# synth-zodiac-taurus-cowbell.net
KiCad netlist of a schematic drawn in EAGLE
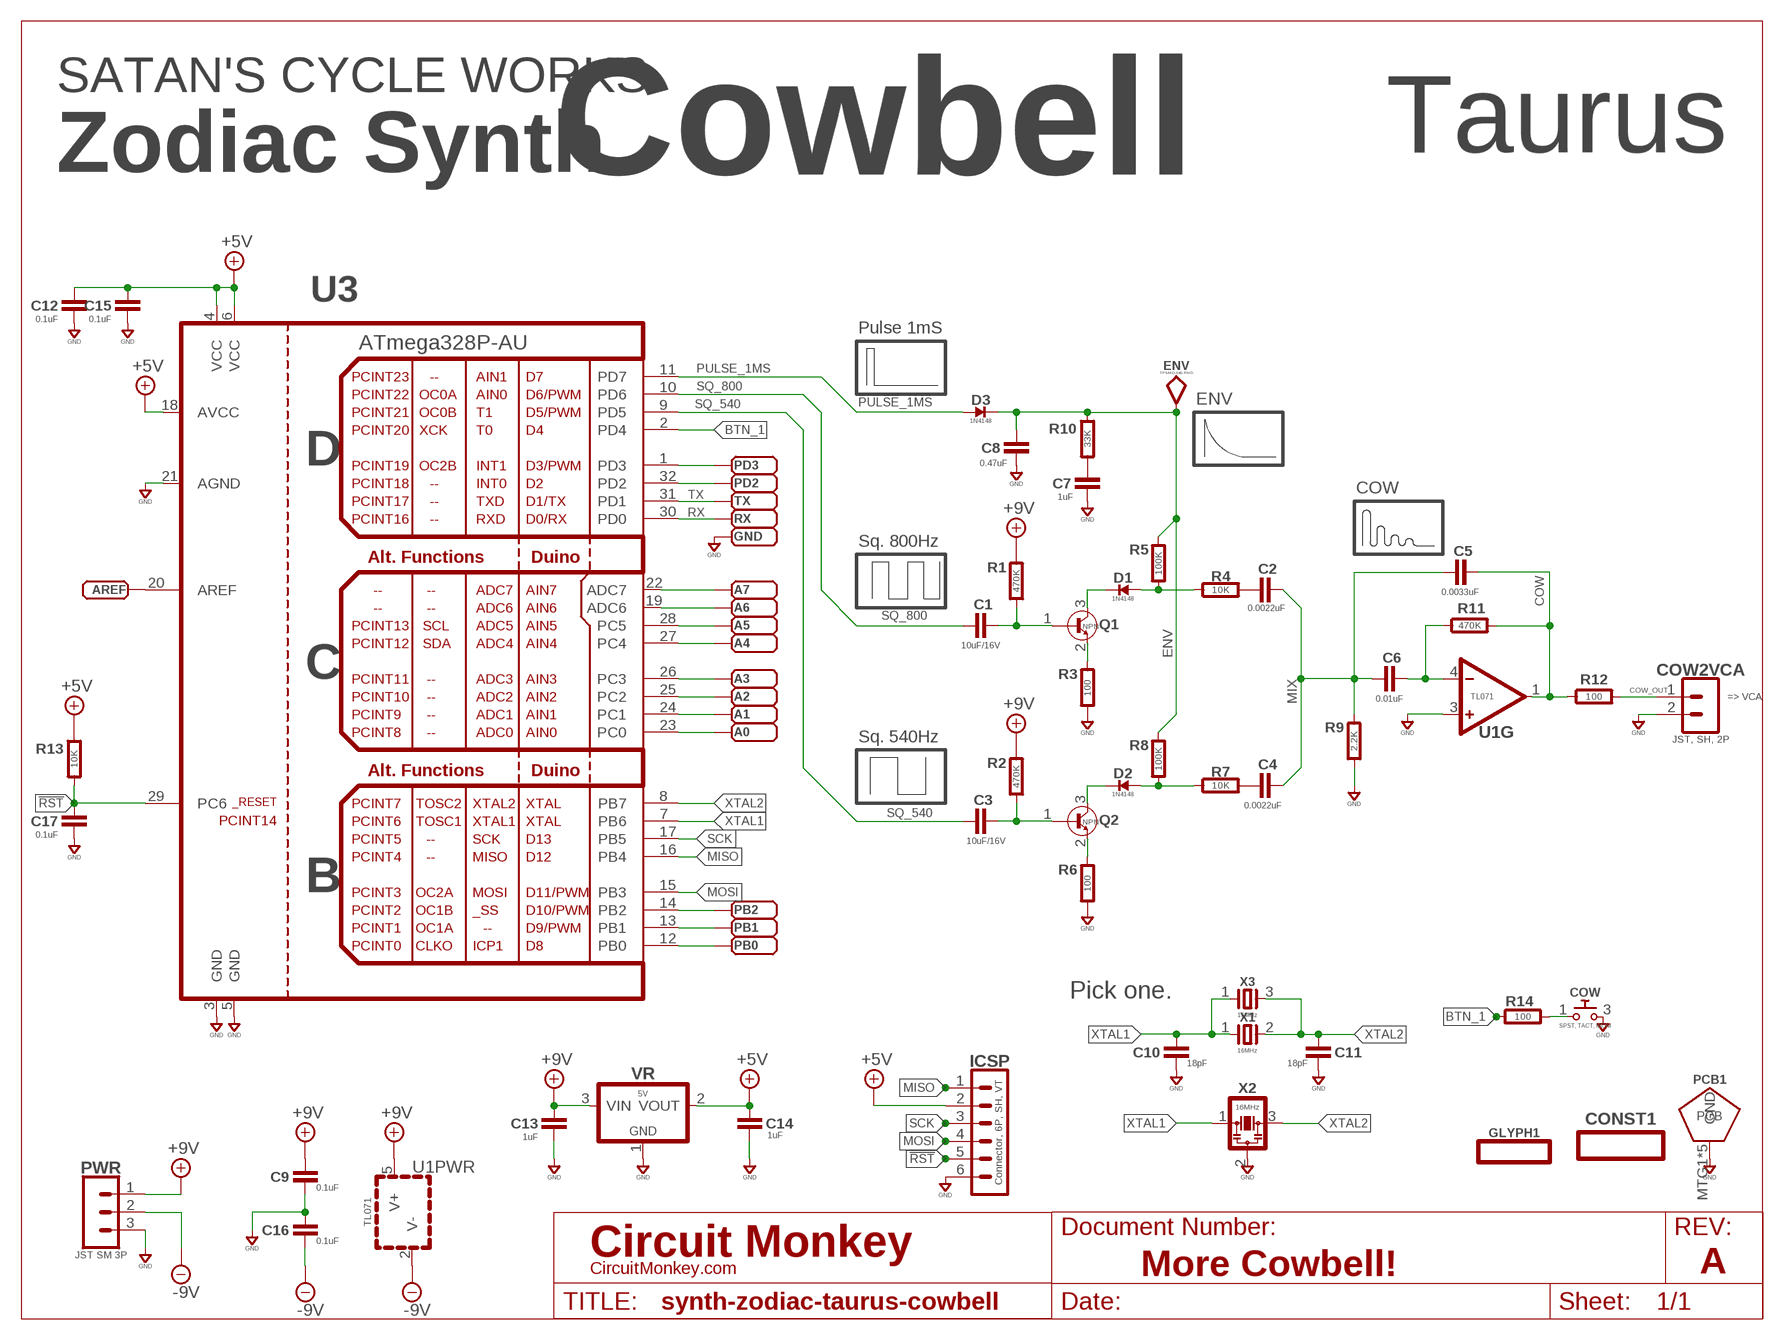
[diagram p0: schematic, sheet 1]

(export (version "E")
  (design (tool "Eeschema 10.0.6"))
  (components
    (comp (ref "A0")
      (value "PADSMD-050X050")
      (footprint "eagle-import:SMD-050X050")
      (libsource (lib "eagle-import") (part "PADSMD-050X050"))
    )
    (comp (ref "A1")
      (value "PADSMD-050X050")
      (footprint "eagle-import:SMD-050X050")
      (libsource (lib "eagle-import") (part "PADSMD-050X050"))
    )
    (comp (ref "A2")
      (value "PADSMD-050X050")
      (footprint "eagle-import:SMD-050X050")
      (libsource (lib "eagle-import") (part "PADSMD-050X050"))
    )
    (comp (ref "A3")
      (value "PADSMD-050X050")
      (footprint "eagle-import:SMD-050X050")
      (libsource (lib "eagle-import") (part "PADSMD-050X050"))
    )
    (comp (ref "A4")
      (value "PADSMD-050X050")
      (footprint "eagle-import:SMD-050X050")
      (libsource (lib "eagle-import") (part "PADSMD-050X050"))
    )
    (comp (ref "A5")
      (value "PADSMD-050X050")
      (footprint "eagle-import:SMD-050X050")
      (libsource (lib "eagle-import") (part "PADSMD-050X050"))
    )
    (comp (ref "A6")
      (value "PADSMD-050X050")
      (footprint "eagle-import:SMD-050X050")
      (libsource (lib "eagle-import") (part "PADSMD-050X050"))
    )
    (comp (ref "A7")
      (value "PADSMD-050X050")
      (footprint "eagle-import:SMD-050X050")
      (libsource (lib "eagle-import") (part "PADSMD-050X050"))
    )
    (comp (ref "AREF")
      (value "PADSMD-050X050")
      (footprint "eagle-import:SMD-050X050")
      (libsource (lib "eagle-import") (part "PADSMD-050X050"))
    )
    (comp (ref "C1")
      (value "10uF/16V")
      (footprint "eagle-import:0603-CAP")
      (libsource (lib "eagle-import") (part "CAPACITOR0603"))
    )
    (comp (ref "C2")
      (value "0.0022uF")
      (footprint "eagle-import:0603-CAP")
      (libsource (lib "eagle-import") (part "CAPACITOR0603"))
    )
    (comp (ref "C3")
      (value "10uF/16V")
      (footprint "eagle-import:0603-CAP")
      (libsource (lib "eagle-import") (part "CAPACITOR0603"))
    )
    (comp (ref "C4")
      (value "0.0022uF")
      (footprint "eagle-import:0603-CAP")
      (libsource (lib "eagle-import") (part "CAPACITOR0603"))
    )
    (comp (ref "C5")
      (value "0.0033uF")
      (footprint "eagle-import:0603-CAP")
      (libsource (lib "eagle-import") (part "CAPACITOR0603"))
    )
    (comp (ref "C6")
      (value "0.01uF")
      (footprint "eagle-import:0603-CAP")
      (libsource (lib "eagle-import") (part "CAPACITOR0603"))
    )
    (comp (ref "C7")
      (value "1uF")
      (footprint "eagle-import:0603-CAP")
      (libsource (lib "eagle-import") (part "CAPACITOR0603"))
    )
    (comp (ref "C8")
      (value "0.47uF")
      (footprint "eagle-import:0603-CAP")
      (libsource (lib "eagle-import") (part "CAPACITOR0603"))
    )
    (comp (ref "C9")
      (value "0.1uF")
      (footprint "eagle-import:0603-CAP")
      (libsource (lib "eagle-import") (part "CAPACITOR0603"))
    )
    (comp (ref "C10")
      (value "18pF")
      (footprint "eagle-import:0603-CAP")
      (libsource (lib "eagle-import") (part "CAPACITOR0603"))
    )
    (comp (ref "C11")
      (value "18pF")
      (footprint "eagle-import:0603-CAP")
      (libsource (lib "eagle-import") (part "CAPACITOR0603"))
    )
    (comp (ref "C12")
      (value "0.1uF")
      (footprint "eagle-import:0603-CAP")
      (libsource (lib "eagle-import") (part "CAPACITOR0603"))
    )
    (comp (ref "C13")
      (value "1uF")
      (footprint "eagle-import:0603-CAP")
      (libsource (lib "eagle-import") (part "CAPACITOR0603"))
    )
    (comp (ref "C14")
      (value "1uF")
      (footprint "eagle-import:0603-CAP")
      (libsource (lib "eagle-import") (part "CAPACITOR0603"))
    )
    (comp (ref "C15")
      (value "0.1uF")
      (footprint "eagle-import:0603-CAP")
      (libsource (lib "eagle-import") (part "CAPACITOR0603"))
    )
    (comp (ref "C16")
      (value "0.1uF")
      (footprint "eagle-import:0603-CAP")
      (libsource (lib "eagle-import") (part "CAPACITOR0603"))
    )
    (comp (ref "C17")
      (value "0.1uF")
      (footprint "eagle-import:0603-CAP")
      (libsource (lib "eagle-import") (part "CAPACITOR0603"))
    )
    (comp (ref "CONST1")
      (value "CONSTELLATION-TAURUS")
      (footprint "eagle-import:TAURUS-CONST")
      (libsource (lib "eagle-import") (part "CONSTELLATION-TAURUS"))
    )
    (comp (ref "COW")
      (value "SPST, TACT, MOM")
      (footprint "eagle-import:B3FS-BACKMOUNT")
      (fields (field (name "MFR") "CK") (field (name "MPN") "B3FS"))
      (libsource (lib "eagle-import") (part "PUSHBTN-MOMB3FS-BLIND"))
    )
    (comp (ref "COW2VCA")
      (value "JST, SH, 2P")
      (footprint "eagle-import:BM02B-SRSS-TB")
      (fields (field (name "MFR") "JST") (field (name "MPN") "BMB02B-SRSS-TB"))
      (libsource (lib "eagle-import") (part "02P-SM-VT-SMT"))
    )
    (comp (ref "D1")
      (value "1N4148")
      (footprint "eagle-import:SOD-123")
      (fields (field (name "MPN") "1N4148W"))
      (libsource (lib "eagle-import") (part "DIODE-1N4148"))
    )
    (comp (ref "D2")
      (value "1N4148")
      (footprint "eagle-import:SOD-123")
      (fields (field (name "MPN") "1N4148W"))
      (libsource (lib "eagle-import") (part "DIODE-1N4148"))
    )
    (comp (ref "D3")
      (value "1N4148")
      (footprint "eagle-import:SOD-123")
      (fields (field (name "MPN") "1N4148W"))
      (libsource (lib "eagle-import") (part "DIODE-1N4148"))
    )
    (comp (ref "ENV")
      (value "TPSMD-040-RND")
      (footprint "eagle-import:SMD-040MIL-RND")
      (libsource (lib "eagle-import") (part "TPSMD-040-RND"))
    )
    (comp (ref "GLYPH1")
      (value "GLYPH-TAURUS")
      (footprint "eagle-import:TAURUS-GLYPH")
      (libsource (lib "eagle-import") (part "GLYPH-TAURUS"))
    )
    (comp (ref "GND")
      (value "PADSMD-050X050")
      (footprint "eagle-import:SMD-050X050")
      (libsource (lib "eagle-import") (part "PADSMD-050X050"))
    )
    (comp (ref "ICSP")
      (value "Connector, 6P, SH, VT")
      (footprint "eagle-import:BM06B-SRSS-TB")
      (fields (field (name "MFR") "JST") (field (name "MPN") "BM06-SRSS-TB"))
      (libsource (lib "eagle-import") (part "06P-SM-VT-SMT"))
    )
    (comp (ref "PB0")
      (value "PADSMD-050X050")
      (footprint "eagle-import:SMD-050X050")
      (libsource (lib "eagle-import") (part "PADSMD-050X050"))
    )
    (comp (ref "PB1")
      (value "PADSMD-050X050")
      (footprint "eagle-import:SMD-050X050")
      (libsource (lib "eagle-import") (part "PADSMD-050X050"))
    )
    (comp (ref "PB2")
      (value "PADSMD-050X050")
      (footprint "eagle-import:SMD-050X050")
      (libsource (lib "eagle-import") (part "PADSMD-050X050"))
    )
    (comp (ref "PCB1")
      (value "PCB FAB")
      (footprint "eagle-import:PENTAGON-40MM-RAD")
      (libsource (lib "eagle-import") (part "PENTAGON-40R"))
    )
    (comp (ref "PD2")
      (value "PADSMD-050X050")
      (footprint "eagle-import:SMD-050X050")
      (libsource (lib "eagle-import") (part "PADSMD-050X050"))
    )
    (comp (ref "PD3")
      (value "PADSMD-050X050")
      (footprint "eagle-import:SMD-050X050")
      (libsource (lib "eagle-import") (part "PADSMD-050X050"))
    )
    (comp (ref "PWR")
      (value "JST SM 3P")
      (footprint "eagle-import:BM03B-SRSS-TB")
      (fields (field (name "MFR") "JST") (field (name "MPN") "BM03B-SRSS-TB"))
      (libsource (lib "eagle-import") (part "03P-SM-VT-SMT"))
    )
    (comp (ref "Q1")
      (value "NPN")
      (footprint "eagle-import:SOT-23")
      (fields (field (name "MFR") "On Semiconductor") (field (name "MPN") "BC846"))
      (libsource (lib "eagle-import") (part "NPN-BC846"))
    )
    (comp (ref "Q2")
      (value "NPN")
      (footprint "eagle-import:SOT-23")
      (fields (field (name "MFR") "On Semiconductor") (field (name "MPN") "BC846"))
      (libsource (lib "eagle-import") (part "NPN-BC846"))
    )
    (comp (ref "R1")
      (value "470K")
      (footprint "eagle-import:0603-RES")
      (libsource (lib "eagle-import") (part "RESISTOR0603"))
    )
    (comp (ref "R2")
      (value "470K")
      (footprint "eagle-import:0603-RES")
      (libsource (lib "eagle-import") (part "RESISTOR0603"))
    )
    (comp (ref "R3")
      (value "100")
      (footprint "eagle-import:0603-RES")
      (libsource (lib "eagle-import") (part "RESISTOR0603"))
    )
    (comp (ref "R4")
      (value "10K")
      (footprint "eagle-import:0603-RES")
      (libsource (lib "eagle-import") (part "RESISTOR0603"))
    )
    (comp (ref "R5")
      (value "100K")
      (footprint "eagle-import:0603-RES")
      (libsource (lib "eagle-import") (part "RESISTOR0603"))
    )
    (comp (ref "R6")
      (value "100")
      (footprint "eagle-import:0603-RES")
      (libsource (lib "eagle-import") (part "RESISTOR0603"))
    )
    (comp (ref "R7")
      (value "10K")
      (footprint "eagle-import:0603-RES")
      (libsource (lib "eagle-import") (part "RESISTOR0603"))
    )
    (comp (ref "R8")
      (value "100K")
      (footprint "eagle-import:0603-RES")
      (libsource (lib "eagle-import") (part "RESISTOR0603"))
    )
    (comp (ref "R9")
      (value "2.2K")
      (footprint "eagle-import:0603-RES")
      (libsource (lib "eagle-import") (part "RESISTOR0603"))
    )
    (comp (ref "R10")
      (value "33K")
      (footprint "eagle-import:0603-RES")
      (libsource (lib "eagle-import") (part "RESISTOR0603"))
    )
    (comp (ref "R11")
      (value "470K")
      (footprint "eagle-import:0603-RES")
      (libsource (lib "eagle-import") (part "RESISTOR0603"))
    )
    (comp (ref "R12")
      (value "100")
      (footprint "eagle-import:0603-RES")
      (libsource (lib "eagle-import") (part "RESISTOR0603"))
    )
    (comp (ref "R13")
      (value "10K")
      (footprint "eagle-import:0603-RES")
      (libsource (lib "eagle-import") (part "RESISTOR0603"))
    )
    (comp (ref "R14")
      (value "100")
      (footprint "eagle-import:0603-RES")
      (libsource (lib "eagle-import") (part "RESISTOR0603"))
    )
    (comp (ref "RX")
      (value "PADSMD-050X050")
      (footprint "eagle-import:SMD-050X050")
      (libsource (lib "eagle-import") (part "PADSMD-050X050"))
    )
    (comp (ref "TX")
      (value "PADSMD-050X050")
      (footprint "eagle-import:SMD-050X050")
      (libsource (lib "eagle-import") (part "PADSMD-050X050"))
    )
    (comp (ref "U1")
      (value "TL071")
      (footprint "eagle-import:SOT-23-5")
      (fields (field (name "MFR") "TI") (field (name "MPN") "TL071HIDBV"))
      (libsource (lib "eagle-import") (part "SINGLE-TL071"))
    )
    (comp (ref "U3")
      (value "ATmega328P-AU")
      (footprint "eagle-import:TQFP-32-08")
      (fields (field (name "MFR") "Atmel") (field (name "MPN") "ATMEGA328P-AU"))
      (libsource (lib "eagle-import") (part "ATMEGA328AU"))
    )
    (comp (ref "VR")
      (value "5V")
      (footprint "eagle-import:SOT-23")
      (fields (field (name "MFR") "Diodes, Inc.") (field (name "MPN") "AP7387-50SA"))
      (libsource (lib "eagle-import") (part "LDO-3P--5V-SOT23"))
    )
    (comp (ref "X1")
      (value "16MHz")
      (footprint "eagle-import:CTS_5X3")
      (fields (field (name "MFR") "CTS") (field (name "MPN") "445C35K16M0000"))
      (libsource (lib "eagle-import") (part "2PCTS_445"))
    )
    (comp (ref "X2")
      (value "16MHz")
      (footprint "eagle-import:CSTE-RESONATOR")
      (fields (field (name "MFR") "Murata") (field (name "MPN") "CSTCE16M"))
      (libsource (lib "eagle-import") (part "RESONATOR-CSTE16"))
    )
    (comp (ref "X3")
      (value "16MHz")
      (footprint "eagle-import:32X25")
      (fields (field (name "MFR") "Epson") (field (name "MPN") "FA-238 16.0000MB-K3"))
      (libsource (lib "eagle-import") (part "2P3.2X2.5"))
    )
  )
  (nets
    (net (code "1") (name "+5V") (class "Default")
      (node (ref "C12") (pin "1") (pinfunction "1_1") (pintype "passive"))
      (node (ref "C14") (pin "1") (pinfunction "1_1") (pintype "passive"))
      (node (ref "C15") (pin "1") (pinfunction "1_1") (pintype "passive"))
      (node (ref "ICSP") (pin "2") (pinfunction "2_2") (pintype "passive"))
      (node (ref "R13") (pin "1") (pinfunction "1_1") (pintype "passive"))
      (node (ref "U3") (pin "18") (pinfunction "AVCC_18") (pintype "power_in"))
      (node (ref "U3") (pin "4") (pinfunction "VCC_4") (pintype "power_in"))
      (node (ref "U3") (pin "6") (pinfunction "VCC_6") (pintype "power_in"))
      (node (ref "VR") (pin "2") (pinfunction "VOUT_2") (pintype "power_in"))
    )
    (net (code "2") (name "+9V") (class "Default")
      (node (ref "C13") (pin "1") (pinfunction "1_1") (pintype "passive"))
      (node (ref "C9") (pin "1") (pinfunction "1_1") (pintype "passive"))
      (node (ref "PWR") (pin "1") (pinfunction "1_1") (pintype "passive"))
      (node (ref "R1") (pin "2") (pinfunction "2_2") (pintype "passive"))
      (node (ref "R2") (pin "2") (pinfunction "2_2") (pintype "passive"))
      (node (ref "U1") (pin "5") (pinfunction "V+_5") (pintype "power_in"))
      (node (ref "VR") (pin "3") (pinfunction "VIN_3") (pintype "power_in"))
    )
    (net (code "3") (name "-9V") (class "Default")
      (node (ref "C16") (pin "2") (pinfunction "2_2") (pintype "passive"))
      (node (ref "PWR") (pin "2") (pinfunction "2_2") (pintype "passive"))
      (node (ref "U1") (pin "2") (pinfunction "V-_2") (pintype "power_in"))
    )
    (net (code "4") (name "/COW") (class "Default")
      (node (ref "C5") (pin "2") (pinfunction "2_2") (pintype "passive"))
      (node (ref "R11") (pin "2") (pinfunction "2_2") (pintype "passive"))
      (node (ref "R12") (pin "1") (pinfunction "1_1") (pintype "passive"))
      (node (ref "U1") (pin "1") (pinfunction "OUT_1") (pintype "output"))
    )
    (net (code "5") (name "/COW_OUT") (class "Default")
      (node (ref "COW2VCA") (pin "1") (pinfunction "1_1") (pintype "passive"))
      (node (ref "R12") (pin "2") (pinfunction "2_2") (pintype "passive"))
    )
    (net (code "6") (name "/ENV") (class "Default")
      (node (ref "C8") (pin "1") (pinfunction "1_1") (pintype "passive"))
      (node (ref "D3") (pin "K") (pinfunction "K_K") (pintype "passive"))
      (node (ref "ENV") (pin "TP") (pinfunction "P$1_TP") (pintype "bidirectional"))
      (node (ref "R10") (pin "1") (pinfunction "1_1") (pintype "passive"))
      (node (ref "R5") (pin "2") (pinfunction "2_2") (pintype "passive"))
      (node (ref "R8") (pin "2") (pinfunction "2_2") (pintype "passive"))
    )
    (net (code "7") (name "/MIX") (class "Default")
      (node (ref "C2") (pin "2") (pinfunction "2_2") (pintype "passive"))
      (node (ref "C4") (pin "2") (pinfunction "2_2") (pintype "passive"))
      (node (ref "C5") (pin "1") (pinfunction "1_1") (pintype "passive"))
      (node (ref "C6") (pin "1") (pinfunction "1_1") (pintype "passive"))
      (node (ref "R9") (pin "2") (pinfunction "2_2") (pintype "passive"))
    )
    (net (code "8") (name "/PULSE_1MS") (class "Default")
      (node (ref "D3") (pin "A") (pinfunction "A_A") (pintype "passive"))
      (node (ref "U3") (pin "11") (pinfunction "PD7_11") (pintype "bidirectional"))
    )
    (net (code "9") (name "/RX") (class "Default")
      (node (ref "RX") (pin "1") (pinfunction "PAD_1") (pintype "bidirectional"))
      (node (ref "U3") (pin "30") (pinfunction "PD0_30") (pintype "bidirectional"))
    )
    (net (code "10") (name "/SQ_540") (class "Default")
      (node (ref "C3") (pin "1") (pinfunction "1_1") (pintype "passive"))
      (node (ref "U3") (pin "9") (pinfunction "PD5_9") (pintype "bidirectional"))
    )
    (net (code "11") (name "/SQ_800") (class "Default")
      (node (ref "C1") (pin "1") (pinfunction "1_1") (pintype "passive"))
      (node (ref "U3") (pin "10") (pinfunction "PD6_10") (pintype "bidirectional"))
    )
    (net (code "12") (name "/TX") (class "Default")
      (node (ref "TX") (pin "1") (pinfunction "PAD_1") (pintype "bidirectional"))
      (node (ref "U3") (pin "31") (pinfunction "PD1_31") (pintype "bidirectional"))
    )
    (net (code "13") (name "/~{RST}") (class "Default")
      (node (ref "C17") (pin "1") (pinfunction "1_1") (pintype "passive"))
      (node (ref "ICSP") (pin "5") (pinfunction "5_5") (pintype "passive"))
      (node (ref "R13") (pin "2") (pinfunction "2_2") (pintype "passive"))
      (node (ref "U3") (pin "29") (pinfunction "PC6_29") (pintype "bidirectional"))
    )
    (net (code "14") (name "BTN_1") (class "Default")
      (node (ref "R14") (pin "1") (pinfunction "1_1") (pintype "passive"))
      (node (ref "U3") (pin "2") (pinfunction "PD4_2") (pintype "bidirectional"))
    )
    (net (code "15") (name "GND") (class "Default")
      (node (ref "C10") (pin "2") (pinfunction "2_2") (pintype "passive"))
      (node (ref "C11") (pin "2") (pinfunction "2_2") (pintype "passive"))
      (node (ref "C12") (pin "2") (pinfunction "2_2") (pintype "passive"))
      (node (ref "C13") (pin "2") (pinfunction "2_2") (pintype "passive"))
      (node (ref "C14") (pin "2") (pinfunction "2_2") (pintype "passive"))
      (node (ref "C15") (pin "2") (pinfunction "2_2") (pintype "passive"))
      (node (ref "C16") (pin "1") (pinfunction "1_1") (pintype "passive"))
      (node (ref "C17") (pin "2") (pinfunction "2_2") (pintype "passive"))
      (node (ref "C7") (pin "2") (pinfunction "2_2") (pintype "passive"))
      (node (ref "C8") (pin "2") (pinfunction "2_2") (pintype "passive"))
      (node (ref "C9") (pin "2") (pinfunction "2_2") (pintype "passive"))
      (node (ref "COW") (pin "3") (pinfunction "2_3") (pintype "passive"))
      (node (ref "COW2VCA") (pin "2") (pinfunction "2_2") (pintype "passive"))
      (node (ref "GND") (pin "1") (pinfunction "PAD_1") (pintype "bidirectional"))
      (node (ref "ICSP") (pin "6") (pinfunction "6_6") (pintype "passive"))
      (node (ref "PCB1") (pin "MTG1") (pinfunction "GND_MTG1") (pintype "bidirectional"))
      (node (ref "PCB1") (pin "MTG2") (pinfunction "GND_MTG2") (pintype "bidirectional"))
      (node (ref "PCB1") (pin "MTG3") (pinfunction "GND_MTG3") (pintype "bidirectional"))
      (node (ref "PCB1") (pin "MTG4") (pinfunction "GND_MTG4") (pintype "bidirectional"))
      (node (ref "PCB1") (pin "MTG5") (pinfunction "GND_MTG5") (pintype "bidirectional"))
      (node (ref "PWR") (pin "3") (pinfunction "3_3") (pintype "passive"))
      (node (ref "R3") (pin "1") (pinfunction "1_1") (pintype "passive"))
      (node (ref "R6") (pin "1") (pinfunction "1_1") (pintype "passive"))
      (node (ref "R9") (pin "1") (pinfunction "1_1") (pintype "passive"))
      (node (ref "U1") (pin "3") (pinfunction "+_3") (pintype "input"))
      (node (ref "U3") (pin "21") (pinfunction "AGND_21") (pintype "power_in"))
      (node (ref "U3") (pin "3") (pinfunction "GND_3") (pintype "power_in"))
      (node (ref "U3") (pin "5") (pinfunction "GND_5") (pintype "power_in"))
      (node (ref "VR") (pin "1") (pinfunction "GND_1") (pintype "power_in"))
      (node (ref "X2") (pin "2") (pinfunction "2_2") (pintype "bidirectional"))
    )
    (net (code "16") (name "MISO") (class "Default")
      (node (ref "ICSP") (pin "1") (pinfunction "1_1") (pintype "passive"))
      (node (ref "U3") (pin "16") (pinfunction "PB4_16") (pintype "bidirectional"))
    )
    (net (code "17") (name "MOSI") (class "Default")
      (node (ref "ICSP") (pin "4") (pinfunction "4_4") (pintype "passive"))
      (node (ref "U3") (pin "15") (pinfunction "PB3_15") (pintype "bidirectional"))
    )
    (net (code "18") (name "Net-(A0-PAD)") (class "Default")
      (node (ref "A0") (pin "1") (pinfunction "PAD_1") (pintype "bidirectional"))
      (node (ref "U3") (pin "23") (pinfunction "PC0_23") (pintype "bidirectional"))
    )
    (net (code "19") (name "Net-(A1-PAD)") (class "Default")
      (node (ref "A1") (pin "1") (pinfunction "PAD_1") (pintype "bidirectional"))
      (node (ref "U3") (pin "24") (pinfunction "PC1_24") (pintype "bidirectional"))
    )
    (net (code "20") (name "Net-(A2-PAD)") (class "Default")
      (node (ref "A2") (pin "1") (pinfunction "PAD_1") (pintype "bidirectional"))
      (node (ref "U3") (pin "25") (pinfunction "PC2_25") (pintype "bidirectional"))
    )
    (net (code "21") (name "Net-(A3-PAD)") (class "Default")
      (node (ref "A3") (pin "1") (pinfunction "PAD_1") (pintype "bidirectional"))
      (node (ref "U3") (pin "26") (pinfunction "PC3_26") (pintype "bidirectional"))
    )
    (net (code "22") (name "Net-(A4-PAD)") (class "Default")
      (node (ref "A4") (pin "1") (pinfunction "PAD_1") (pintype "bidirectional"))
      (node (ref "U3") (pin "27") (pinfunction "PC4_27") (pintype "bidirectional"))
    )
    (net (code "23") (name "Net-(A5-PAD)") (class "Default")
      (node (ref "A5") (pin "1") (pinfunction "PAD_1") (pintype "bidirectional"))
      (node (ref "U3") (pin "28") (pinfunction "PC5_28") (pintype "bidirectional"))
    )
    (net (code "24") (name "Net-(A6-PAD)") (class "Default")
      (node (ref "A6") (pin "1") (pinfunction "PAD_1") (pintype "bidirectional"))
      (node (ref "U3") (pin "19") (pinfunction "ADC6_19") (pintype "bidirectional"))
    )
    (net (code "25") (name "Net-(A7-PAD)") (class "Default")
      (node (ref "A7") (pin "1") (pinfunction "PAD_1") (pintype "bidirectional"))
      (node (ref "U3") (pin "22") (pinfunction "ADC7_22") (pintype "bidirectional"))
    )
    (net (code "26") (name "Net-(AREF-PAD)") (class "Default")
      (node (ref "AREF") (pin "1") (pinfunction "PAD_1") (pintype "bidirectional"))
      (node (ref "U3") (pin "20") (pinfunction "AREF_20") (pintype "input"))
    )
    (net (code "27") (name "Net-(C2-Pad1)") (class "Default")
      (node (ref "C2") (pin "1") (pinfunction "1_1") (pintype "passive"))
      (node (ref "R4") (pin "2") (pinfunction "2_2") (pintype "passive"))
    )
    (net (code "28") (name "Net-(C4-Pad1)") (class "Default")
      (node (ref "C4") (pin "1") (pinfunction "1_1") (pintype "passive"))
      (node (ref "R7") (pin "2") (pinfunction "2_2") (pintype "passive"))
    )
    (net (code "29") (name "Net-(C7-Pad1)") (class "Default")
      (node (ref "C7") (pin "1") (pinfunction "1_1") (pintype "passive"))
      (node (ref "R10") (pin "2") (pinfunction "2_2") (pintype "passive"))
    )
    (net (code "30") (name "Net-(COW-Pad1)") (class "Default")
      (node (ref "COW") (pin "1") (pinfunction "1_1") (pintype "passive"))
      (node (ref "R14") (pin "2") (pinfunction "2_2") (pintype "passive"))
    )
    (net (code "31") (name "Net-(D1-PadA)") (class "Default")
      (node (ref "D1") (pin "A") (pinfunction "A_A") (pintype "passive"))
      (node (ref "R4") (pin "1") (pinfunction "1_1") (pintype "passive"))
      (node (ref "R5") (pin "1") (pinfunction "1_1") (pintype "passive"))
    )
    (net (code "32") (name "Net-(D2-PadA)") (class "Default")
      (node (ref "D2") (pin "A") (pinfunction "A_A") (pintype "passive"))
      (node (ref "R7") (pin "1") (pinfunction "1_1") (pintype "passive"))
      (node (ref "R8") (pin "1") (pinfunction "1_1") (pintype "passive"))
    )
    (net (code "33") (name "Net-(PB0-PAD)") (class "Default")
      (node (ref "PB0") (pin "1") (pinfunction "PAD_1") (pintype "bidirectional"))
      (node (ref "U3") (pin "12") (pinfunction "PB0_12") (pintype "bidirectional"))
    )
    (net (code "34") (name "Net-(PB1-PAD)") (class "Default")
      (node (ref "PB1") (pin "1") (pinfunction "PAD_1") (pintype "bidirectional"))
      (node (ref "U3") (pin "13") (pinfunction "PB1_13") (pintype "bidirectional"))
    )
    (net (code "35") (name "Net-(PB2-PAD)") (class "Default")
      (node (ref "PB2") (pin "1") (pinfunction "PAD_1") (pintype "bidirectional"))
      (node (ref "U3") (pin "14") (pinfunction "PB2_14") (pintype "bidirectional"))
    )
    (net (code "36") (name "Net-(PD2-PAD)") (class "Default")
      (node (ref "PD2") (pin "1") (pinfunction "PAD_1") (pintype "bidirectional"))
      (node (ref "U3") (pin "32") (pinfunction "PD2_32") (pintype "bidirectional"))
    )
    (net (code "37") (name "Net-(PD3-PAD)") (class "Default")
      (node (ref "PD3") (pin "1") (pinfunction "PAD_1") (pintype "bidirectional"))
      (node (ref "U3") (pin "1") (pinfunction "PD3_1") (pintype "bidirectional"))
    )
    (net (code "38") (name "Net-(Q1-BASE)") (class "Default")
      (node (ref "C1") (pin "2") (pinfunction "2_2") (pintype "passive"))
      (node (ref "Q1") (pin "1") (pinfunction "BASE_1") (pintype "bidirectional"))
      (node (ref "R1") (pin "1") (pinfunction "1_1") (pintype "passive"))
    )
    (net (code "39") (name "Net-(Q1-COLLECTOR)") (class "Default")
      (node (ref "D1") (pin "K") (pinfunction "K_K") (pintype "passive"))
      (node (ref "Q1") (pin "3") (pinfunction "COLLECTOR_3") (pintype "bidirectional"))
    )
    (net (code "40") (name "Net-(Q1-EMITTER)") (class "Default")
      (node (ref "Q1") (pin "2") (pinfunction "EMITTER_2") (pintype "bidirectional"))
      (node (ref "R3") (pin "2") (pinfunction "2_2") (pintype "passive"))
    )
    (net (code "41") (name "Net-(Q2-BASE)") (class "Default")
      (node (ref "C3") (pin "2") (pinfunction "2_2") (pintype "passive"))
      (node (ref "Q2") (pin "1") (pinfunction "BASE_1") (pintype "bidirectional"))
      (node (ref "R2") (pin "1") (pinfunction "1_1") (pintype "passive"))
    )
    (net (code "42") (name "Net-(Q2-COLLECTOR)") (class "Default")
      (node (ref "D2") (pin "K") (pinfunction "K_K") (pintype "passive"))
      (node (ref "Q2") (pin "3") (pinfunction "COLLECTOR_3") (pintype "bidirectional"))
    )
    (net (code "43") (name "Net-(Q2-EMITTER)") (class "Default")
      (node (ref "Q2") (pin "2") (pinfunction "EMITTER_2") (pintype "bidirectional"))
      (node (ref "R6") (pin "2") (pinfunction "2_2") (pintype "passive"))
    )
    (net (code "44") (name "Net-(U1A--)") (class "Default")
      (node (ref "C6") (pin "2") (pinfunction "2_2") (pintype "passive"))
      (node (ref "R11") (pin "1") (pinfunction "1_1") (pintype "passive"))
      (node (ref "U1") (pin "4") (pinfunction "-_4") (pintype "input"))
    )
    (net (code "45") (name "SCK") (class "Default")
      (node (ref "ICSP") (pin "3") (pinfunction "3_3") (pintype "passive"))
      (node (ref "U3") (pin "17") (pinfunction "PB5_17") (pintype "bidirectional"))
    )
    (net (code "46") (name "XTAL1") (class "Default")
      (node (ref "C10") (pin "1") (pinfunction "1_1") (pintype "passive"))
      (node (ref "U3") (pin "7") (pinfunction "PB6_7") (pintype "bidirectional"))
      (node (ref "X1") (pin "1") (pinfunction "P$1_1") (pintype "passive"))
      (node (ref "X2") (pin "1") (pinfunction "1_1") (pintype "bidirectional"))
      (node (ref "X3") (pin "1") (pinfunction "P$1_1") (pintype "passive"))
    )
    (net (code "47") (name "XTAL2") (class "Default")
      (node (ref "C11") (pin "1") (pinfunction "1_1") (pintype "passive"))
      (node (ref "U3") (pin "8") (pinfunction "PB7_8") (pintype "bidirectional"))
      (node (ref "X1") (pin "2") (pinfunction "P$2_2") (pintype "passive"))
      (node (ref "X2") (pin "3") (pinfunction "3_3") (pintype "bidirectional"))
      (node (ref "X3") (pin "3") (pinfunction "P$2_3") (pintype "passive"))
    )
  )
)
